# battey.net
KiCad netlist of a schematic drawn in EAGLE
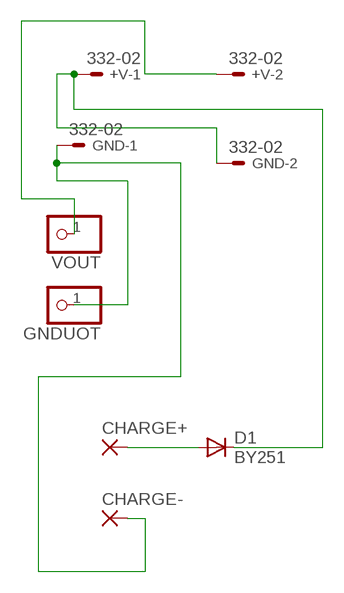
[diagram p0: schematic, sheet 1]

(export (version "E")
  (design (tool "Eeschema 10.0.6"))
  (components
    (comp (ref "+V")
      (value "332-02")
      (footprint "eagle-import:332-02")
      (libsource (lib "eagle-import") (part "332-02"))
    )
    (comp (ref "CHARGE+")
      (value "2,54/1,0")
      (footprint "eagle-import:2,54_1,0")
      (libsource (lib "eagle-import") (part "2,54/1,0"))
    )
    (comp (ref "CHARGE-")
      (value "2,54/1,0")
      (footprint "eagle-import:2,54_1,0")
      (libsource (lib "eagle-import") (part "2,54/1,0"))
    )
    (comp (ref "D1")
      (value "BY251")
      (footprint "eagle-import:DO201-15")
      (libsource (lib "eagle-import") (part "BY251"))
    )
    (comp (ref "GND")
      (value "332-02")
      (footprint "eagle-import:332-02")
      (libsource (lib "eagle-import") (part "332-02"))
    )
    (comp (ref "GNDUOT")
      (value "PINHD-1X1")
      (footprint "eagle-import:1X01")
      (libsource (lib "eagle-import") (part "PINHD-1X1"))
    )
    (comp (ref "VOUT")
      (value "PINHD-1X1")
      (footprint "eagle-import:1X01")
      (libsource (lib "eagle-import") (part "PINHD-1X1"))
    )
  )
  (nets
    (net (code "1") (name "Net-(+VA-S)") (class "Default")
      (node (ref "+V") (pin "1") (pinfunction "S_1") (pintype "passive"))
      (node (ref "D1") (pin "C") (pinfunction "C_C") (pintype "passive"))
      (node (ref "GND") (pin "2") (pinfunction "S_2") (pintype "passive"))
    )
    (net (code "2") (name "Net-(+VB-S)") (class "Default")
      (node (ref "+V") (pin "2") (pinfunction "S_2") (pintype "passive"))
      (node (ref "VOUT") (pin "1") (pinfunction "1_1") (pintype "passive"))
    )
    (net (code "3") (name "Net-(CHARGE+-P)") (class "Default")
      (node (ref "CHARGE+") (pin "1") (pinfunction "P_1") (pintype "passive"))
      (node (ref "D1") (pin "A") (pinfunction "A_A") (pintype "passive"))
    )
    (net (code "4") (name "Net-(CHARGE--P)") (class "Default")
      (node (ref "CHARGE-") (pin "1") (pinfunction "P_1") (pintype "passive"))
      (node (ref "GND") (pin "1") (pinfunction "S_1") (pintype "passive"))
      (node (ref "GNDUOT") (pin "1") (pinfunction "1_1") (pintype "passive"))
    )
  )
)
